# leddriverX3.net
KiCad netlist of a schematic drawn in EAGLE
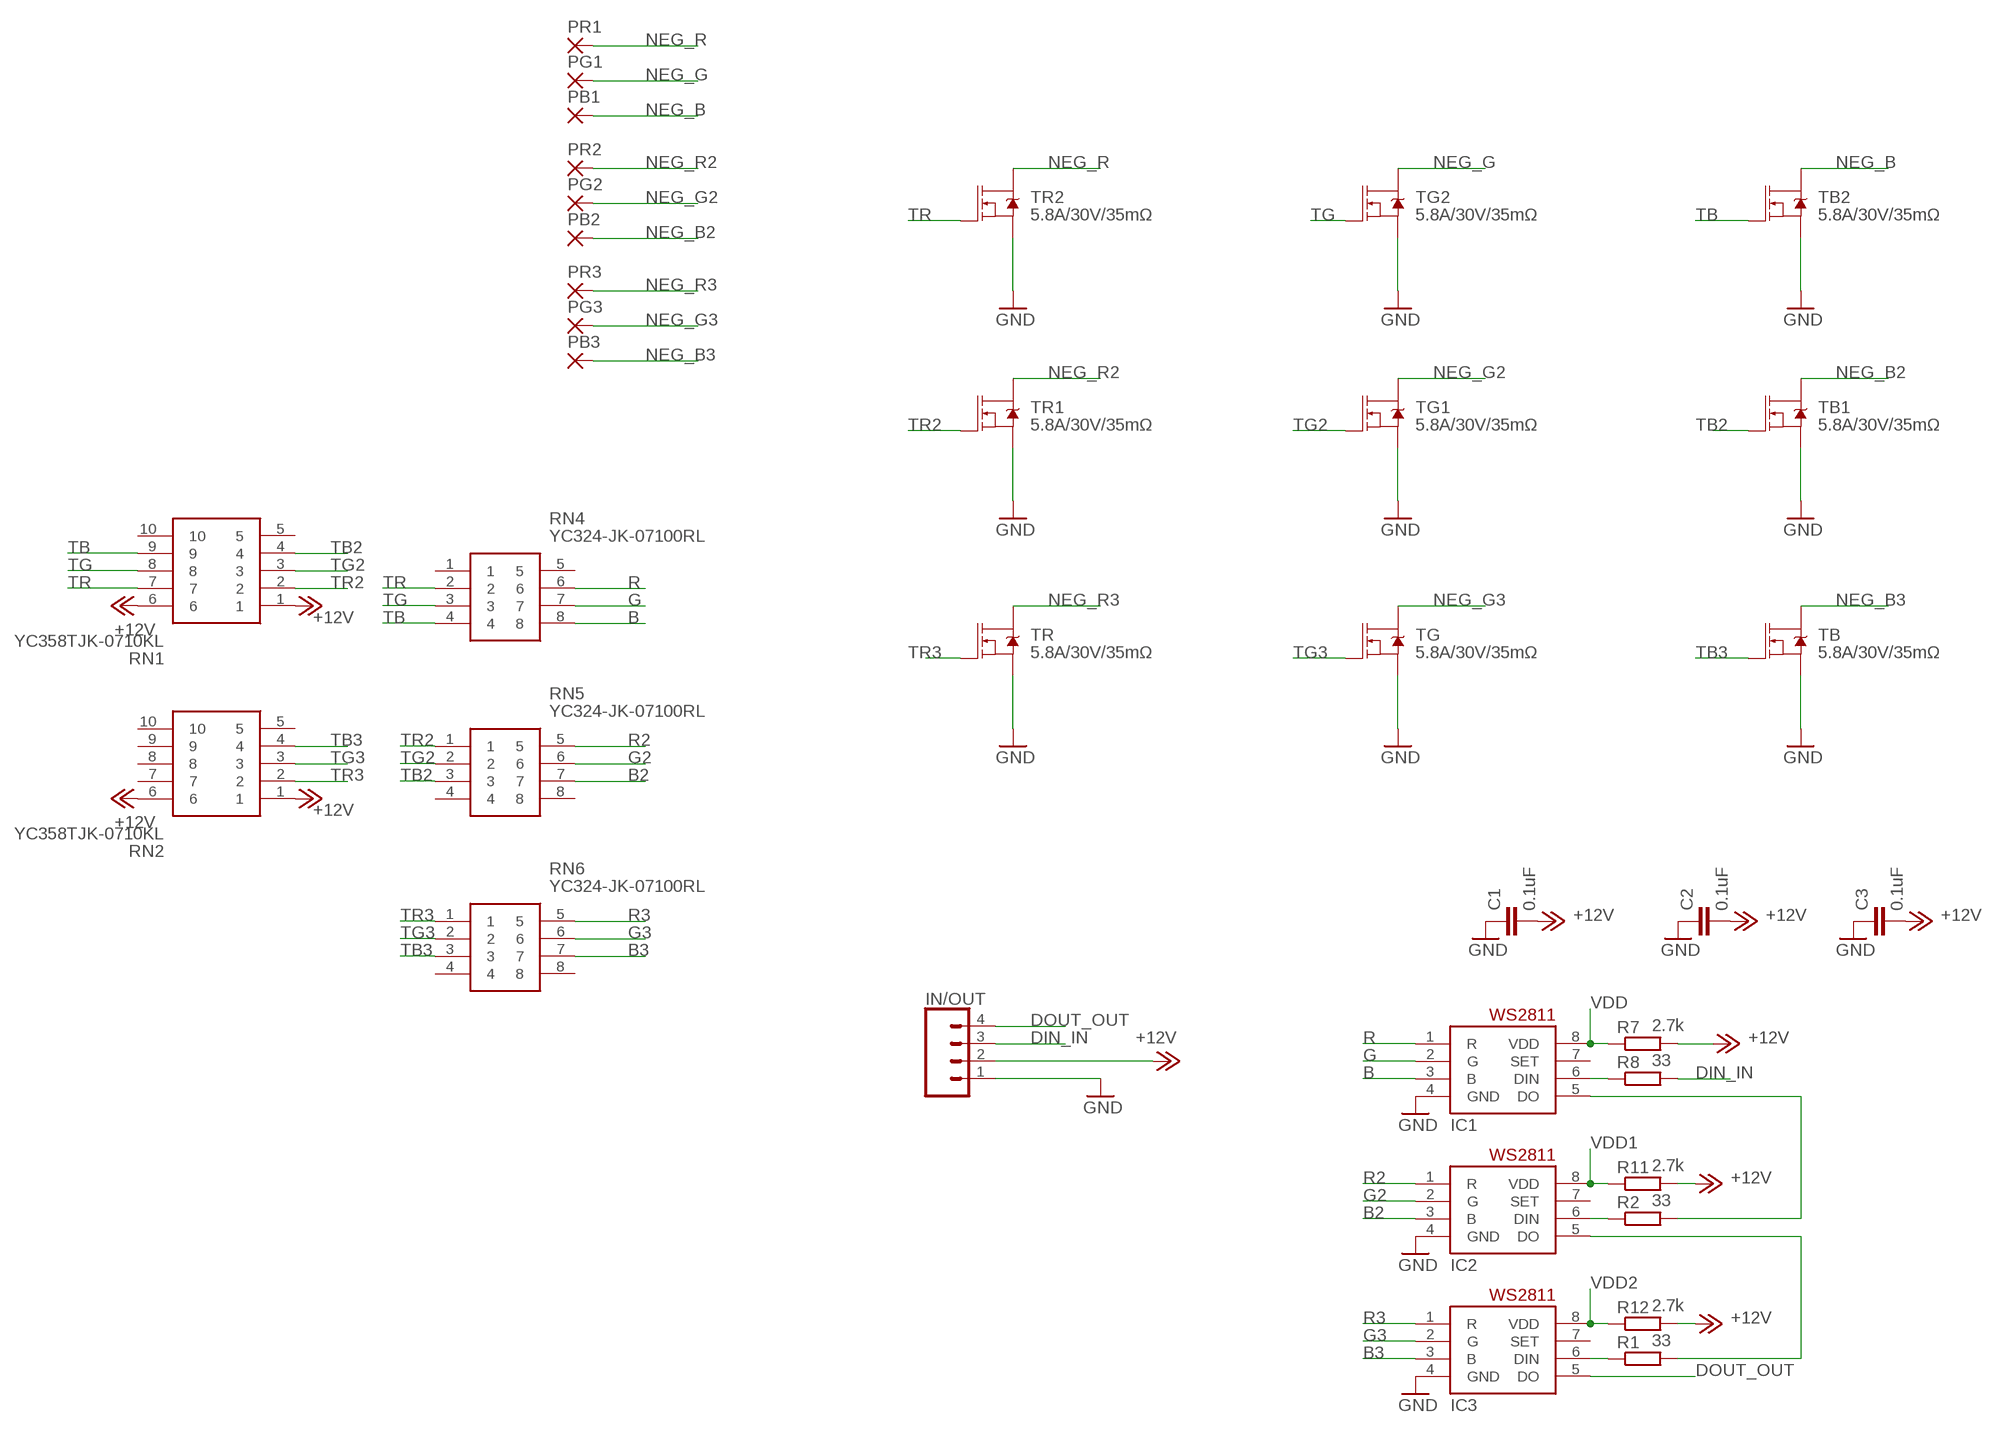
[diagram p0: schematic, sheet 1]

(export (version "E")
  (design (tool "Eeschema 10.0.6"))
  (components
    (comp (ref "C1")
      (value "0.1uF")
      (footprint "eagle-import:C1206")
      (libsource (lib "eagle-import") (part "C-EUC1206"))
    )
    (comp (ref "C2")
      (value "0.1uF")
      (footprint "eagle-import:C1206")
      (libsource (lib "eagle-import") (part "C-EUC1206"))
    )
    (comp (ref "C3")
      (value "0.1uF")
      (footprint "eagle-import:C1206")
      (libsource (lib "eagle-import") (part "C-EUC1206"))
    )
    (comp (ref "IC1")
      (value "WS2811-SOP8")
      (footprint "eagle-import:SO08-SKINNYPADS")
      (libsource (lib "eagle-import") (part "WS2811-SOP8"))
    )
    (comp (ref "IC2")
      (value "WS2811-SOP8")
      (footprint "eagle-import:SO08-SKINNYPADS")
      (libsource (lib "eagle-import") (part "WS2811-SOP8"))
    )
    (comp (ref "IC3")
      (value "WS2811-SOP8")
      (footprint "eagle-import:SO08-SKINNYPADS")
      (libsource (lib "eagle-import") (part "WS2811-SOP8"))
    )
    (comp (ref "IN/OUT")
      (value "CONN_04LONGPADS")
      (footprint "eagle-import:1X04_LONGPADS")
      (libsource (lib "eagle-import") (part "CONN_04LONGPADS"))
    )
    (comp (ref "PB1")
      (value "3,81/1,4")
      (footprint "eagle-import:3,81_1,4")
      (libsource (lib "eagle-import") (part "3,81/1,4"))
    )
    (comp (ref "PB2")
      (value "3,81/1,4")
      (footprint "eagle-import:3,81_1,4")
      (libsource (lib "eagle-import") (part "3,81/1,4"))
    )
    (comp (ref "PB3")
      (value "3,81/1,4")
      (footprint "eagle-import:3,81_1,4")
      (libsource (lib "eagle-import") (part "3,81/1,4"))
    )
    (comp (ref "PG1")
      (value "3,81/1,4")
      (footprint "eagle-import:3,81_1,4")
      (libsource (lib "eagle-import") (part "3,81/1,4"))
    )
    (comp (ref "PG2")
      (value "3,81/1,4")
      (footprint "eagle-import:3,81_1,4")
      (libsource (lib "eagle-import") (part "3,81/1,4"))
    )
    (comp (ref "PG3")
      (value "3,81/1,4")
      (footprint "eagle-import:3,81_1,4")
      (libsource (lib "eagle-import") (part "3,81/1,4"))
    )
    (comp (ref "PR1")
      (value "3,81/1,4")
      (footprint "eagle-import:3,81_1,4")
      (libsource (lib "eagle-import") (part "3,81/1,4"))
    )
    (comp (ref "PR2")
      (value "3,81/1,4")
      (footprint "eagle-import:3,81_1,4")
      (libsource (lib "eagle-import") (part "3,81/1,4"))
    )
    (comp (ref "PR3")
      (value "3,81/1,4")
      (footprint "eagle-import:3,81_1,4")
      (libsource (lib "eagle-import") (part "3,81/1,4"))
    )
    (comp (ref "R1")
      (value "33")
      (footprint "eagle-import:R0805")
      (libsource (lib "eagle-import") (part "R-EU_R0805"))
    )
    (comp (ref "R2")
      (value "33")
      (footprint "eagle-import:R0805")
      (libsource (lib "eagle-import") (part "R-EU_R0805"))
    )
    (comp (ref "R7")
      (value "2.7k")
      (footprint "eagle-import:R0805")
      (libsource (lib "eagle-import") (part "R-EU_R0805"))
    )
    (comp (ref "R8")
      (value "33")
      (footprint "eagle-import:R0805")
      (libsource (lib "eagle-import") (part "R-EU_R0805"))
    )
    (comp (ref "R11")
      (value "2.7k")
      (footprint "eagle-import:R0805")
      (libsource (lib "eagle-import") (part "R-EU_R0805"))
    )
    (comp (ref "R12")
      (value "2.7k")
      (footprint "eagle-import:R0805")
      (libsource (lib "eagle-import") (part "R-EU_R0805"))
    )
    (comp (ref "RN1")
      (value "YC358TJK-0710KL")
      (footprint "eagle-import:YC358T")
      (fields (field (name "MOUSER_PART_NUMBER") "603-YC358TJK-0710KL"))
      (libsource (lib "eagle-import") (part "YC358TJK-0710KL"))
    )
    (comp (ref "RN2")
      (value "YC358TJK-0710KL")
      (footprint "eagle-import:YC358T")
      (fields (field (name "MOUSER_PART_NUMBER") "603-YC358TJK-0710KL"))
      (libsource (lib "eagle-import") (part "YC358TJK-0710KL"))
    )
    (comp (ref "RN4")
      (value "YC324-JK-07100RL")
      (footprint "eagle-import:YC324JK07100RL")
      (fields (field (name "MOUSER_PART_NUMBER") "603-YC324-JK-07100RL"))
      (libsource (lib "eagle-import") (part "YC324-JK-07100RL"))
    )
    (comp (ref "RN5")
      (value "YC324-JK-07100RL")
      (footprint "eagle-import:YC324JK07100RL")
      (fields (field (name "MOUSER_PART_NUMBER") "603-YC324-JK-07100RL"))
      (libsource (lib "eagle-import") (part "YC324-JK-07100RL"))
    )
    (comp (ref "RN6")
      (value "YC324-JK-07100RL")
      (footprint "eagle-import:YC324JK07100RL")
      (fields (field (name "MOUSER_PART_NUMBER") "603-YC324-JK-07100RL"))
      (libsource (lib "eagle-import") (part "YC324-JK-07100RL"))
    )
    (comp (ref "TB")
      (value "5.8A/30V/35mΩ")
      (footprint "eagle-import:SOT23-3")
      (libsource (lib "eagle-import") (part "MOSFET-NCH-AO3404A"))
    )
    (comp (ref "TB1")
      (value "5.8A/30V/35mΩ")
      (footprint "eagle-import:SOT23-3")
      (libsource (lib "eagle-import") (part "MOSFET-NCH-AO3404A"))
    )
    (comp (ref "TB2")
      (value "5.8A/30V/35mΩ")
      (footprint "eagle-import:SOT23-3")
      (libsource (lib "eagle-import") (part "MOSFET-NCH-AO3404A"))
    )
    (comp (ref "TG")
      (value "5.8A/30V/35mΩ")
      (footprint "eagle-import:SOT23-3")
      (libsource (lib "eagle-import") (part "MOSFET-NCH-AO3404A"))
    )
    (comp (ref "TG1")
      (value "5.8A/30V/35mΩ")
      (footprint "eagle-import:SOT23-3")
      (libsource (lib "eagle-import") (part "MOSFET-NCH-AO3404A"))
    )
    (comp (ref "TG2")
      (value "5.8A/30V/35mΩ")
      (footprint "eagle-import:SOT23-3")
      (libsource (lib "eagle-import") (part "MOSFET-NCH-AO3404A"))
    )
    (comp (ref "TR")
      (value "5.8A/30V/35mΩ")
      (footprint "eagle-import:SOT23-3")
      (libsource (lib "eagle-import") (part "MOSFET-NCH-AO3404A"))
    )
    (comp (ref "TR1")
      (value "5.8A/30V/35mΩ")
      (footprint "eagle-import:SOT23-3")
      (libsource (lib "eagle-import") (part "MOSFET-NCH-AO3404A"))
    )
    (comp (ref "TR2")
      (value "5.8A/30V/35mΩ")
      (footprint "eagle-import:SOT23-3")
      (libsource (lib "eagle-import") (part "MOSFET-NCH-AO3404A"))
    )
  )
  (nets
    (net (code "1") (name "+12V") (class "Default")
      (node (ref "C1") (pin "2") (pinfunction "2_2") (pintype "passive"))
      (node (ref "C2") (pin "2") (pinfunction "2_2") (pintype "passive"))
      (node (ref "C3") (pin "2") (pinfunction "2_2") (pintype "passive"))
      (node (ref "IN/OUT") (pin "2") (pinfunction "2_2") (pintype "passive"))
      (node (ref "R11") (pin "2") (pinfunction "2_2") (pintype "passive"))
      (node (ref "R12") (pin "2") (pinfunction "2_2") (pintype "passive"))
      (node (ref "R7") (pin "2") (pinfunction "2_2") (pintype "passive"))
      (node (ref "RN1") (pin "1") (pinfunction "1_1") (pintype "bidirectional"))
      (node (ref "RN1") (pin "6") (pinfunction "6_6") (pintype "bidirectional"))
      (node (ref "RN2") (pin "1") (pinfunction "1_1") (pintype "bidirectional"))
      (node (ref "RN2") (pin "6") (pinfunction "6_6") (pintype "bidirectional"))
    )
    (net (code "2") (name "/B") (class "Default")
      (node (ref "IC1") (pin "3") (pinfunction "B_3") (pintype "open_collector"))
      (node (ref "RN4") (pin "8") (pinfunction "8_8") (pintype "bidirectional"))
    )
    (net (code "3") (name "/B2") (class "Default")
      (node (ref "IC2") (pin "3") (pinfunction "B_3") (pintype "open_collector"))
      (node (ref "RN5") (pin "7") (pinfunction "7_7") (pintype "bidirectional"))
    )
    (net (code "4") (name "/B3") (class "Default")
      (node (ref "IC3") (pin "3") (pinfunction "B_3") (pintype "open_collector"))
      (node (ref "RN6") (pin "7") (pinfunction "7_7") (pintype "bidirectional"))
    )
    (net (code "5") (name "/DIN_IN") (class "Default")
      (node (ref "IN/OUT") (pin "3") (pinfunction "3_3") (pintype "passive"))
      (node (ref "R8") (pin "2") (pinfunction "2_2") (pintype "passive"))
    )
    (net (code "6") (name "/DOUT_OUT") (class "Default")
      (node (ref "IC3") (pin "5") (pinfunction "DO_5") (pintype "output"))
      (node (ref "IN/OUT") (pin "4") (pinfunction "4_4") (pintype "passive"))
    )
    (net (code "7") (name "/G") (class "Default")
      (node (ref "IC1") (pin "2") (pinfunction "G_2") (pintype "open_collector"))
      (node (ref "RN4") (pin "7") (pinfunction "7_7") (pintype "bidirectional"))
    )
    (net (code "8") (name "/G2") (class "Default")
      (node (ref "IC2") (pin "2") (pinfunction "G_2") (pintype "open_collector"))
      (node (ref "RN5") (pin "6") (pinfunction "6_6") (pintype "bidirectional"))
    )
    (net (code "9") (name "/G3") (class "Default")
      (node (ref "IC3") (pin "2") (pinfunction "G_2") (pintype "open_collector"))
      (node (ref "RN6") (pin "6") (pinfunction "6_6") (pintype "bidirectional"))
    )
    (net (code "10") (name "/NEG_B") (class "Default")
      (node (ref "PB1") (pin "1") (pinfunction "P_1") (pintype "passive"))
      (node (ref "TB2") (pin "3") (pinfunction "D_3") (pintype "bidirectional"))
    )
    (net (code "11") (name "/NEG_B2") (class "Default")
      (node (ref "PB2") (pin "1") (pinfunction "P_1") (pintype "passive"))
      (node (ref "TB1") (pin "3") (pinfunction "D_3") (pintype "bidirectional"))
    )
    (net (code "12") (name "/NEG_B3") (class "Default")
      (node (ref "PB3") (pin "1") (pinfunction "P_1") (pintype "passive"))
      (node (ref "TB") (pin "3") (pinfunction "D_3") (pintype "bidirectional"))
    )
    (net (code "13") (name "/NEG_G") (class "Default")
      (node (ref "PG1") (pin "1") (pinfunction "P_1") (pintype "passive"))
      (node (ref "TG2") (pin "3") (pinfunction "D_3") (pintype "bidirectional"))
    )
    (net (code "14") (name "/NEG_G2") (class "Default")
      (node (ref "PG2") (pin "1") (pinfunction "P_1") (pintype "passive"))
      (node (ref "TG1") (pin "3") (pinfunction "D_3") (pintype "bidirectional"))
    )
    (net (code "15") (name "/NEG_G3") (class "Default")
      (node (ref "PG3") (pin "1") (pinfunction "P_1") (pintype "passive"))
      (node (ref "TG") (pin "3") (pinfunction "D_3") (pintype "bidirectional"))
    )
    (net (code "16") (name "/NEG_R") (class "Default")
      (node (ref "PR1") (pin "1") (pinfunction "P_1") (pintype "passive"))
      (node (ref "TR2") (pin "3") (pinfunction "D_3") (pintype "bidirectional"))
    )
    (net (code "17") (name "/NEG_R2") (class "Default")
      (node (ref "PR2") (pin "1") (pinfunction "P_1") (pintype "passive"))
      (node (ref "TR1") (pin "3") (pinfunction "D_3") (pintype "bidirectional"))
    )
    (net (code "18") (name "/NEG_R3") (class "Default")
      (node (ref "PR3") (pin "1") (pinfunction "P_1") (pintype "passive"))
      (node (ref "TR") (pin "3") (pinfunction "D_3") (pintype "bidirectional"))
    )
    (net (code "19") (name "/R") (class "Default")
      (node (ref "IC1") (pin "1") (pinfunction "R_1") (pintype "open_collector"))
      (node (ref "RN4") (pin "6") (pinfunction "6_6") (pintype "bidirectional"))
    )
    (net (code "20") (name "/R2") (class "Default")
      (node (ref "IC2") (pin "1") (pinfunction "R_1") (pintype "open_collector"))
      (node (ref "RN5") (pin "5") (pinfunction "5_5") (pintype "bidirectional"))
    )
    (net (code "21") (name "/R3") (class "Default")
      (node (ref "IC3") (pin "1") (pinfunction "R_1") (pintype "open_collector"))
      (node (ref "RN6") (pin "5") (pinfunction "5_5") (pintype "bidirectional"))
    )
    (net (code "22") (name "/TB") (class "Default")
      (node (ref "RN1") (pin "9") (pinfunction "9_9") (pintype "bidirectional"))
      (node (ref "RN4") (pin "4") (pinfunction "4_4") (pintype "bidirectional"))
      (node (ref "TB2") (pin "1") (pinfunction "G_1") (pintype "bidirectional"))
    )
    (net (code "23") (name "/TB2") (class "Default")
      (node (ref "RN1") (pin "4") (pinfunction "4_4") (pintype "bidirectional"))
      (node (ref "RN5") (pin "3") (pinfunction "3_3") (pintype "bidirectional"))
      (node (ref "TB1") (pin "1") (pinfunction "G_1") (pintype "bidirectional"))
    )
    (net (code "24") (name "/TB3") (class "Default")
      (node (ref "RN2") (pin "4") (pinfunction "4_4") (pintype "bidirectional"))
      (node (ref "RN6") (pin "3") (pinfunction "3_3") (pintype "bidirectional"))
      (node (ref "TB") (pin "1") (pinfunction "G_1") (pintype "bidirectional"))
    )
    (net (code "25") (name "/TG") (class "Default")
      (node (ref "RN1") (pin "8") (pinfunction "8_8") (pintype "bidirectional"))
      (node (ref "RN4") (pin "3") (pinfunction "3_3") (pintype "bidirectional"))
      (node (ref "TG2") (pin "1") (pinfunction "G_1") (pintype "bidirectional"))
    )
    (net (code "26") (name "/TG2") (class "Default")
      (node (ref "RN1") (pin "3") (pinfunction "3_3") (pintype "bidirectional"))
      (node (ref "RN5") (pin "2") (pinfunction "2_2") (pintype "bidirectional"))
      (node (ref "TG1") (pin "1") (pinfunction "G_1") (pintype "bidirectional"))
    )
    (net (code "27") (name "/TG3") (class "Default")
      (node (ref "RN2") (pin "3") (pinfunction "3_3") (pintype "bidirectional"))
      (node (ref "RN6") (pin "2") (pinfunction "2_2") (pintype "bidirectional"))
      (node (ref "TG") (pin "1") (pinfunction "G_1") (pintype "bidirectional"))
    )
    (net (code "28") (name "/TR") (class "Default")
      (node (ref "RN1") (pin "7") (pinfunction "7_7") (pintype "bidirectional"))
      (node (ref "RN4") (pin "2") (pinfunction "2_2") (pintype "bidirectional"))
      (node (ref "TR2") (pin "1") (pinfunction "G_1") (pintype "bidirectional"))
    )
    (net (code "29") (name "/TR2") (class "Default")
      (node (ref "RN1") (pin "2") (pinfunction "2_2") (pintype "bidirectional"))
      (node (ref "RN5") (pin "1") (pinfunction "1_1") (pintype "bidirectional"))
      (node (ref "TR1") (pin "1") (pinfunction "G_1") (pintype "bidirectional"))
    )
    (net (code "30") (name "/TR3") (class "Default")
      (node (ref "RN2") (pin "2") (pinfunction "2_2") (pintype "bidirectional"))
      (node (ref "RN6") (pin "1") (pinfunction "1_1") (pintype "bidirectional"))
      (node (ref "TR") (pin "1") (pinfunction "G_1") (pintype "bidirectional"))
    )
    (net (code "31") (name "/VDD") (class "Default")
      (node (ref "IC1") (pin "8") (pinfunction "VDD_8") (pintype "power_in"))
      (node (ref "R7") (pin "1") (pinfunction "1_1") (pintype "passive"))
    )
    (net (code "32") (name "/VDD1") (class "Default")
      (node (ref "IC2") (pin "8") (pinfunction "VDD_8") (pintype "power_in"))
      (node (ref "R11") (pin "1") (pinfunction "1_1") (pintype "passive"))
    )
    (net (code "33") (name "/VDD2") (class "Default")
      (node (ref "IC3") (pin "8") (pinfunction "VDD_8") (pintype "power_in"))
      (node (ref "R12") (pin "1") (pinfunction "1_1") (pintype "passive"))
    )
    (net (code "34") (name "GND") (class "Default")
      (node (ref "C1") (pin "1") (pinfunction "1_1") (pintype "passive"))
      (node (ref "C2") (pin "1") (pinfunction "1_1") (pintype "passive"))
      (node (ref "C3") (pin "1") (pinfunction "1_1") (pintype "passive"))
      (node (ref "IC1") (pin "4") (pinfunction "GND_4") (pintype "power_in"))
      (node (ref "IC2") (pin "4") (pinfunction "GND_4") (pintype "power_in"))
      (node (ref "IC3") (pin "4") (pinfunction "GND_4") (pintype "power_in"))
      (node (ref "IN/OUT") (pin "1") (pinfunction "1_1") (pintype "passive"))
      (node (ref "TB") (pin "2") (pinfunction "S_2") (pintype "bidirectional"))
      (node (ref "TB1") (pin "2") (pinfunction "S_2") (pintype "bidirectional"))
      (node (ref "TB2") (pin "2") (pinfunction "S_2") (pintype "bidirectional"))
      (node (ref "TG") (pin "2") (pinfunction "S_2") (pintype "bidirectional"))
      (node (ref "TG1") (pin "2") (pinfunction "S_2") (pintype "bidirectional"))
      (node (ref "TG2") (pin "2") (pinfunction "S_2") (pintype "bidirectional"))
      (node (ref "TR") (pin "2") (pinfunction "S_2") (pintype "bidirectional"))
      (node (ref "TR1") (pin "2") (pinfunction "S_2") (pintype "bidirectional"))
      (node (ref "TR2") (pin "2") (pinfunction "S_2") (pintype "bidirectional"))
    )
    (net (code "35") (name "Net-(IC1-DIN)") (class "Default")
      (node (ref "IC1") (pin "6") (pinfunction "DIN_6") (pintype "input"))
      (node (ref "R8") (pin "1") (pinfunction "1_1") (pintype "passive"))
    )
    (net (code "36") (name "Net-(IC1-DO)") (class "Default")
      (node (ref "IC1") (pin "5") (pinfunction "DO_5") (pintype "output"))
      (node (ref "R2") (pin "2") (pinfunction "2_2") (pintype "passive"))
    )
    (net (code "37") (name "Net-(IC2-DIN)") (class "Default")
      (node (ref "IC2") (pin "6") (pinfunction "DIN_6") (pintype "input"))
      (node (ref "R2") (pin "1") (pinfunction "1_1") (pintype "passive"))
    )
    (net (code "38") (name "Net-(IC2-DO)") (class "Default")
      (node (ref "IC2") (pin "5") (pinfunction "DO_5") (pintype "output"))
      (node (ref "R1") (pin "2") (pinfunction "2_2") (pintype "passive"))
    )
    (net (code "39") (name "Net-(IC3-DIN)") (class "Default")
      (node (ref "IC3") (pin "6") (pinfunction "DIN_6") (pintype "input"))
      (node (ref "R1") (pin "1") (pinfunction "1_1") (pintype "passive"))
    )
    (net (code "40") (name "unconnected-(IC1-SET-Pad7)") (class "Default")
      (node (ref "IC1") (pin "7") (pinfunction "SET_7") (pintype "input"))
    )
    (net (code "41") (name "unconnected-(IC2-SET-Pad7)") (class "Default")
      (node (ref "IC2") (pin "7") (pinfunction "SET_7") (pintype "input"))
    )
    (net (code "42") (name "unconnected-(IC3-SET-Pad7)") (class "Default")
      (node (ref "IC3") (pin "7") (pinfunction "SET_7") (pintype "input"))
    )
    (net (code "43") (name "unconnected-(RN1-Pad5)") (class "Default")
      (node (ref "RN1") (pin "5") (pinfunction "5_5") (pintype "bidirectional"))
    )
    (net (code "44") (name "unconnected-(RN1-Pad10)") (class "Default")
      (node (ref "RN1") (pin "10") (pinfunction "10_10") (pintype "bidirectional"))
    )
    (net (code "45") (name "unconnected-(RN2-Pad5)") (class "Default")
      (node (ref "RN2") (pin "5") (pinfunction "5_5") (pintype "bidirectional"))
    )
    (net (code "46") (name "unconnected-(RN2-Pad7)") (class "Default")
      (node (ref "RN2") (pin "7") (pinfunction "7_7") (pintype "bidirectional"))
    )
    (net (code "47") (name "unconnected-(RN2-Pad8)") (class "Default")
      (node (ref "RN2") (pin "8") (pinfunction "8_8") (pintype "bidirectional"))
    )
    (net (code "48") (name "unconnected-(RN2-Pad9)") (class "Default")
      (node (ref "RN2") (pin "9") (pinfunction "9_9") (pintype "bidirectional"))
    )
    (net (code "49") (name "unconnected-(RN2-Pad10)") (class "Default")
      (node (ref "RN2") (pin "10") (pinfunction "10_10") (pintype "bidirectional"))
    )
    (net (code "50") (name "unconnected-(RN4-Pad1)") (class "Default")
      (node (ref "RN4") (pin "1") (pinfunction "1_1") (pintype "bidirectional"))
    )
    (net (code "51") (name "unconnected-(RN4-Pad5)") (class "Default")
      (node (ref "RN4") (pin "5") (pinfunction "5_5") (pintype "bidirectional"))
    )
    (net (code "52") (name "unconnected-(RN5-Pad4)") (class "Default")
      (node (ref "RN5") (pin "4") (pinfunction "4_4") (pintype "bidirectional"))
    )
    (net (code "53") (name "unconnected-(RN5-Pad8)") (class "Default")
      (node (ref "RN5") (pin "8") (pinfunction "8_8") (pintype "bidirectional"))
    )
    (net (code "54") (name "unconnected-(RN6-Pad4)") (class "Default")
      (node (ref "RN6") (pin "4") (pinfunction "4_4") (pintype "bidirectional"))
    )
    (net (code "55") (name "unconnected-(RN6-Pad8)") (class "Default")
      (node (ref "RN6") (pin "8") (pinfunction "8_8") (pintype "bidirectional"))
    )
  )
)
